# MP3_8xMulti_V1_0.net
KiCad netlist of a schematic drawn in EAGLE
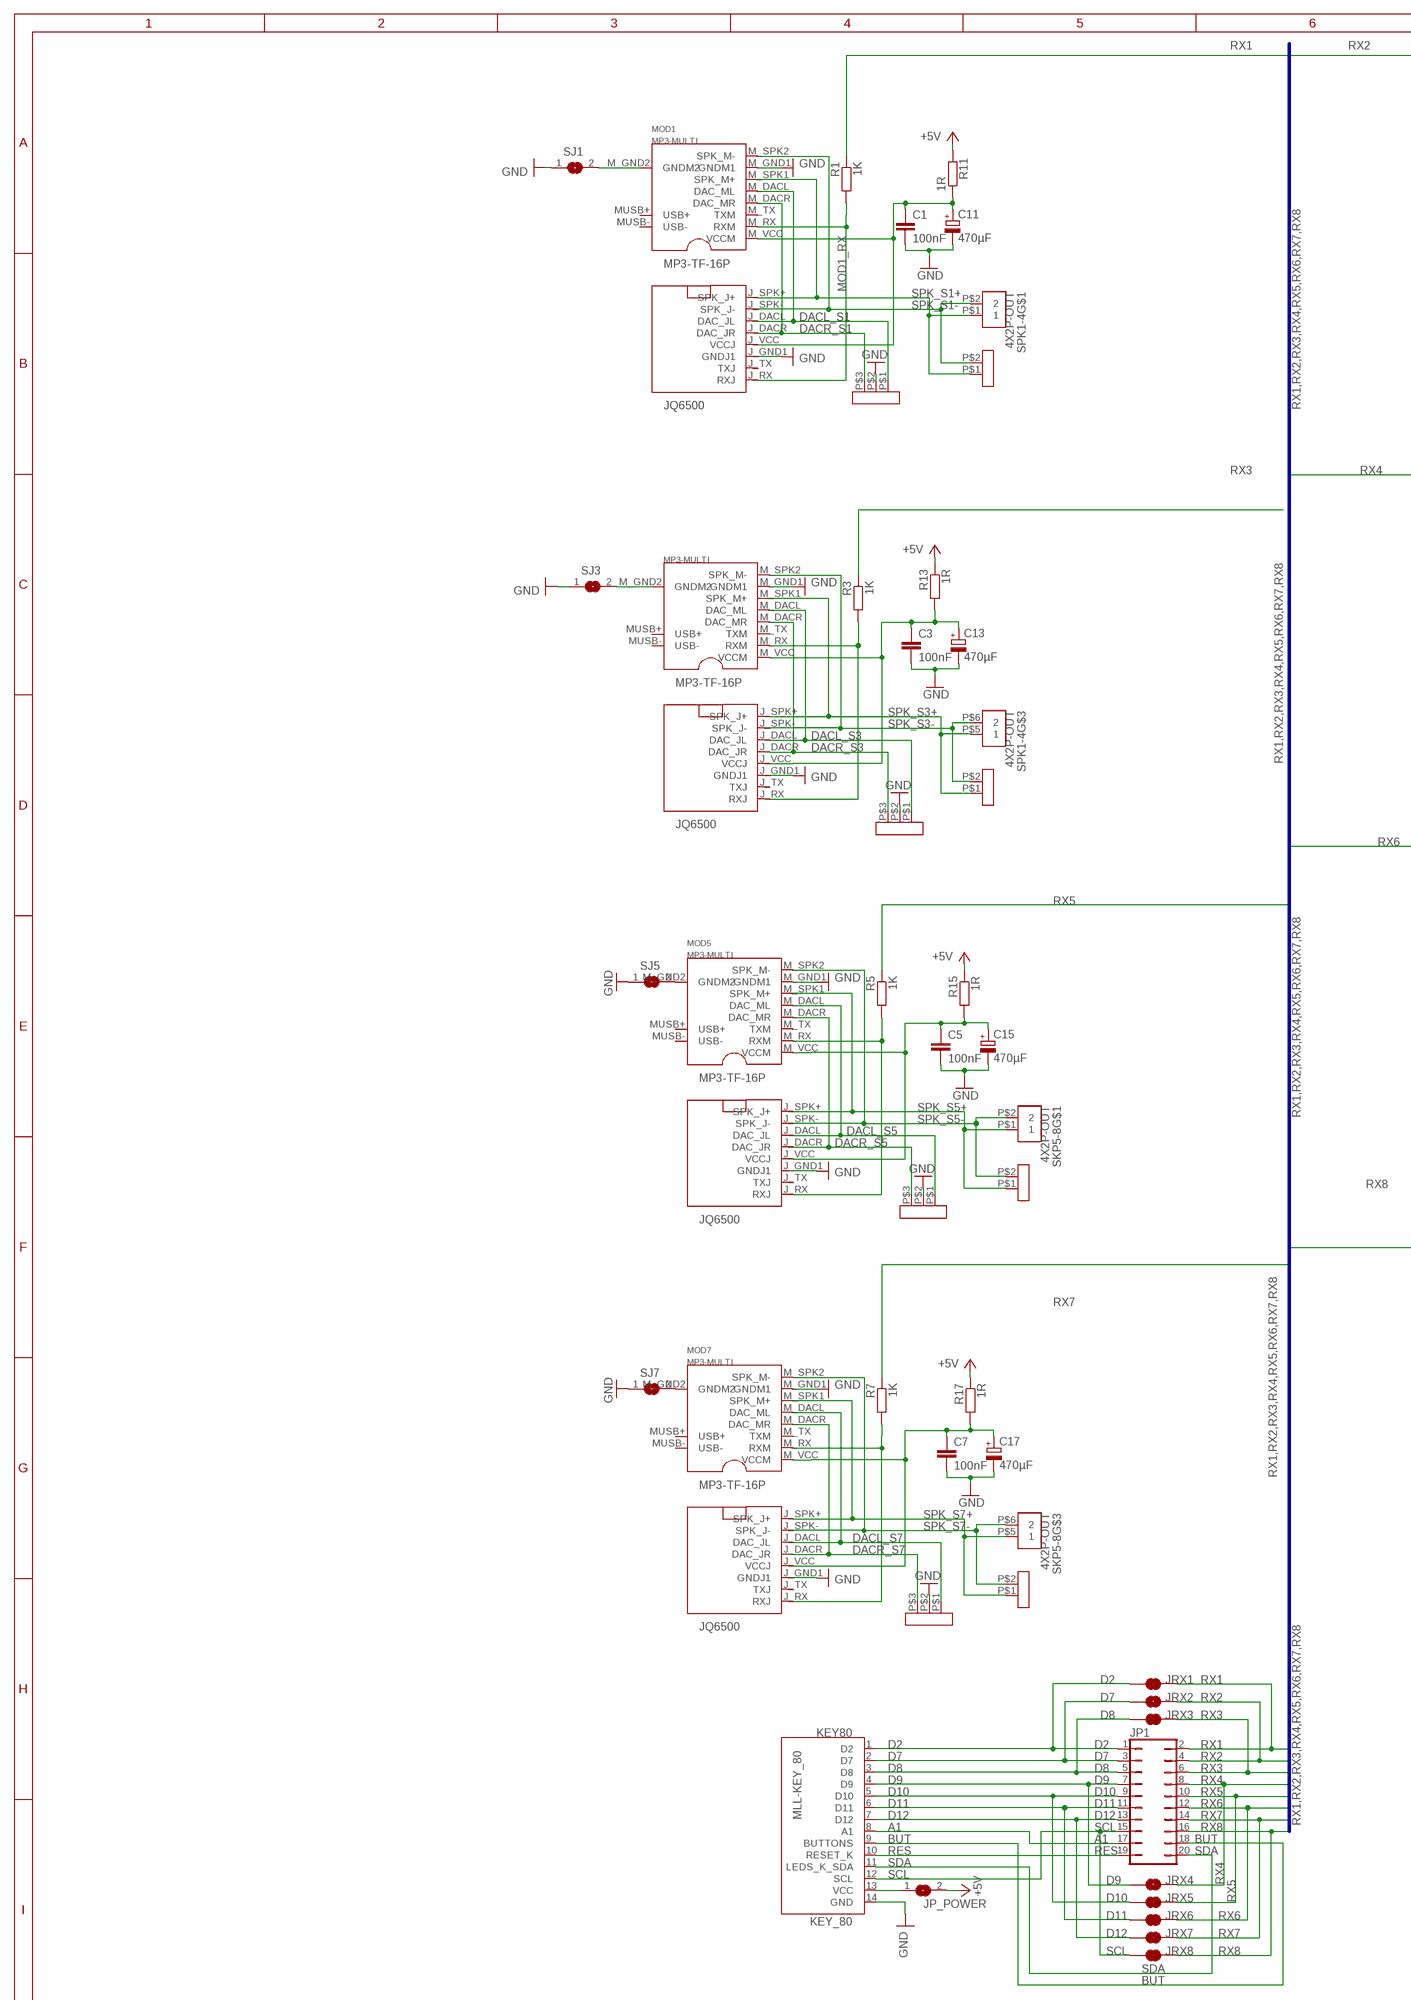
[diagram p0: schematic, sheet 1, part 1 of 2]
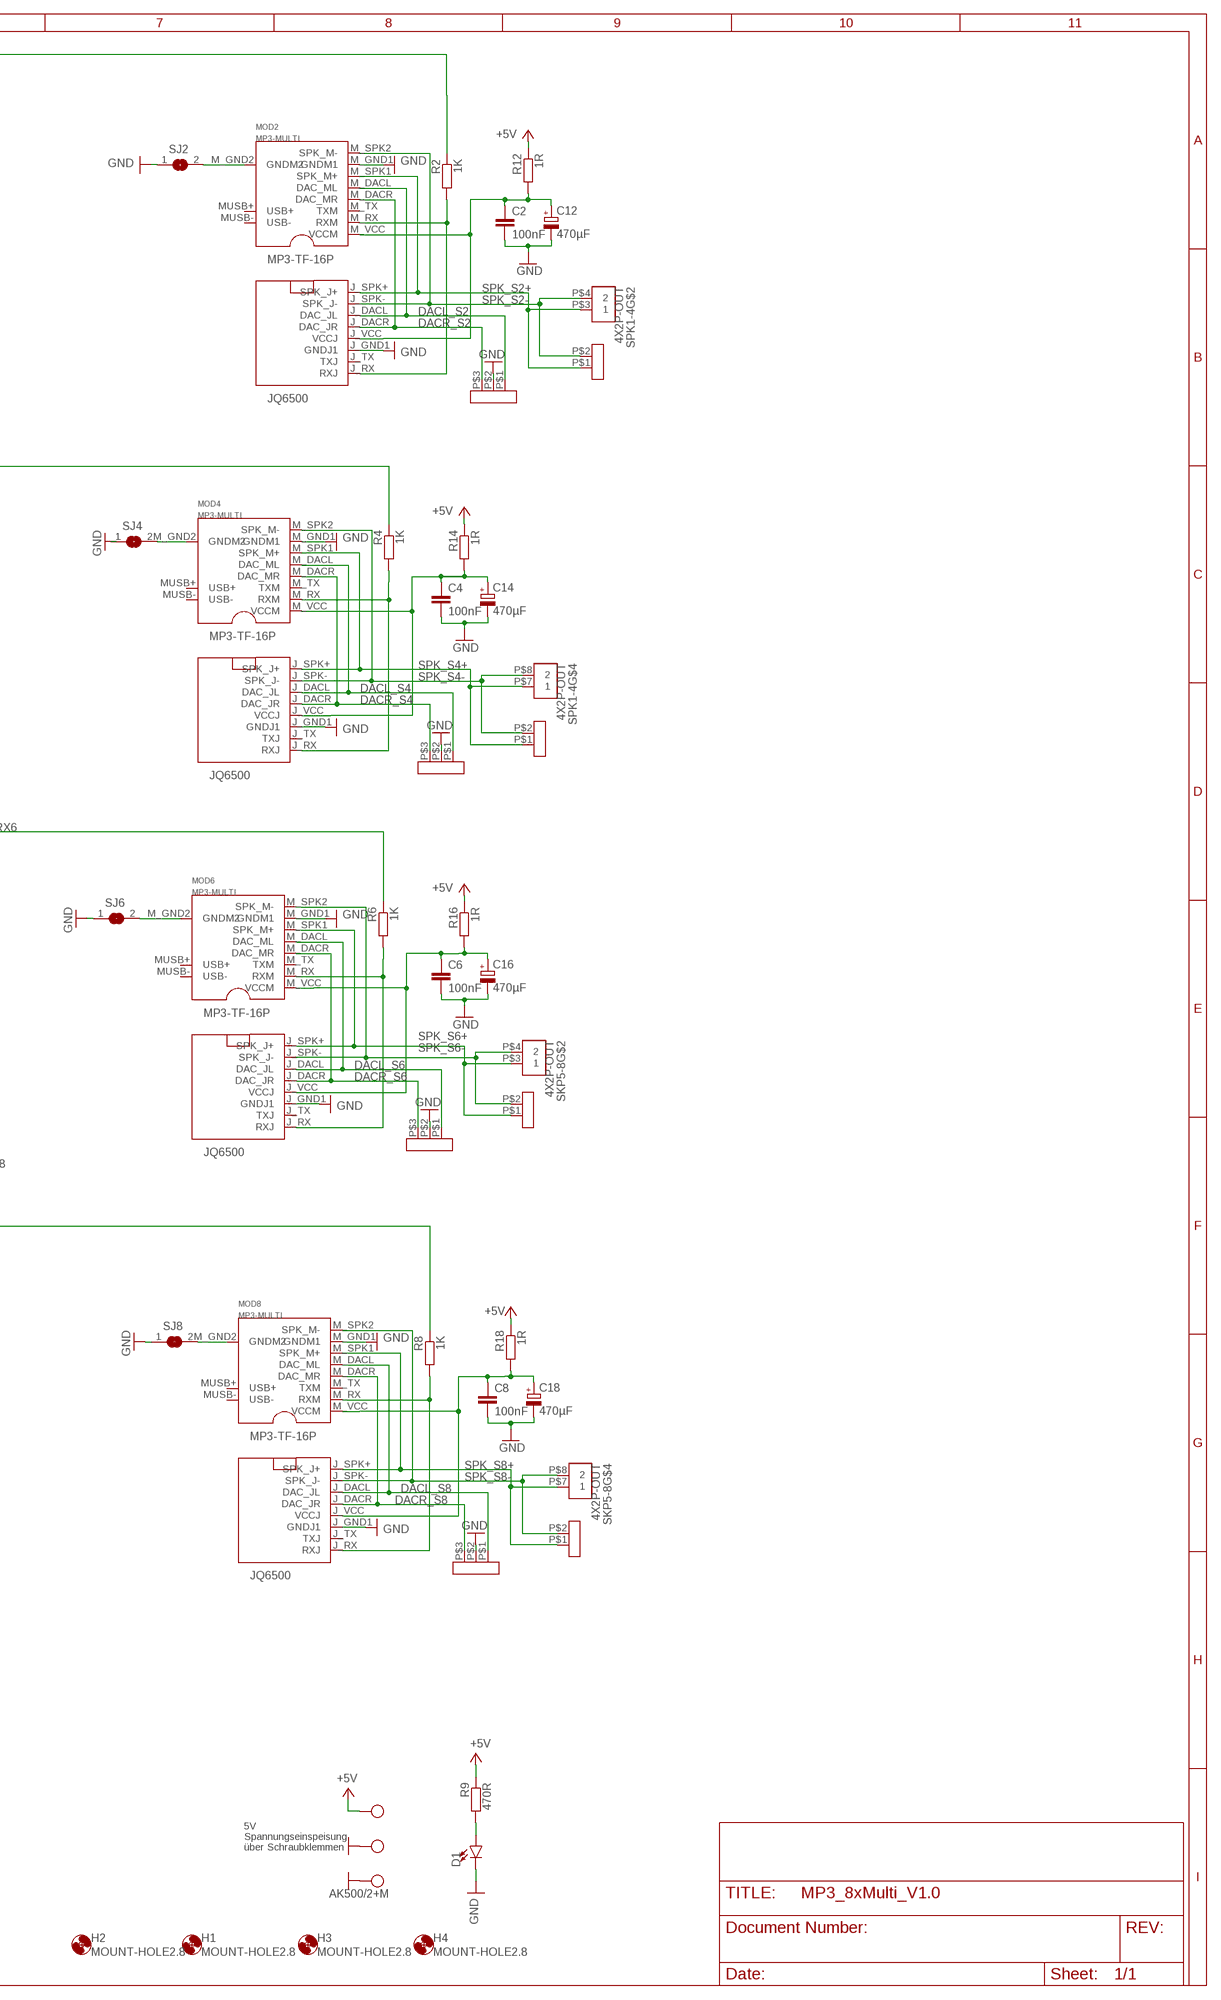
[diagram p1: schematic, sheet 1, part 2 of 2]

(export (version "E")
  (design (tool "Eeschema 10.0.6"))
  (components
    (comp (ref "C1")
      (value "100nF")
      (footprint "eagle-import:C025-025X050")
      (libsource (lib "eagle-import") (part "C-EU025-025X050"))
    )
    (comp (ref "C2")
      (value "100nF")
      (footprint "eagle-import:C025-025X050")
      (libsource (lib "eagle-import") (part "C-EU025-025X050"))
    )
    (comp (ref "C3")
      (value "100nF")
      (footprint "eagle-import:C025-025X050")
      (libsource (lib "eagle-import") (part "C-EU025-025X050"))
    )
    (comp (ref "C4")
      (value "100nF")
      (footprint "eagle-import:C025-025X050")
      (libsource (lib "eagle-import") (part "C-EU025-025X050"))
    )
    (comp (ref "C5")
      (value "100nF")
      (footprint "eagle-import:C025-025X050")
      (libsource (lib "eagle-import") (part "C-EU025-025X050"))
    )
    (comp (ref "C6")
      (value "100nF")
      (footprint "eagle-import:C025-025X050")
      (libsource (lib "eagle-import") (part "C-EU025-025X050"))
    )
    (comp (ref "C7")
      (value "100nF")
      (footprint "eagle-import:C025-025X050")
      (libsource (lib "eagle-import") (part "C-EU025-025X050"))
    )
    (comp (ref "C8")
      (value "100nF")
      (footprint "eagle-import:C025-025X050")
      (libsource (lib "eagle-import") (part "C-EU025-025X050"))
    )
    (comp (ref "C11")
      (value "470µF")
      (footprint "eagle-import:E5-8,5")
      (libsource (lib "eagle-import") (part "CPOL-EUE5-8.5"))
    )
    (comp (ref "C12")
      (value "470µF")
      (footprint "eagle-import:E5-8,5")
      (libsource (lib "eagle-import") (part "CPOL-EUE5-8.5"))
    )
    (comp (ref "C13")
      (value "470µF")
      (footprint "eagle-import:E5-8,5")
      (libsource (lib "eagle-import") (part "CPOL-EUE5-8.5"))
    )
    (comp (ref "C14")
      (value "470µF")
      (footprint "eagle-import:E5-8,5")
      (libsource (lib "eagle-import") (part "CPOL-EUE5-8.5"))
    )
    (comp (ref "C15")
      (value "470µF")
      (footprint "eagle-import:E5-8,5")
      (libsource (lib "eagle-import") (part "CPOL-EUE5-8.5"))
    )
    (comp (ref "C16")
      (value "470µF")
      (footprint "eagle-import:E5-8,5")
      (libsource (lib "eagle-import") (part "CPOL-EUE5-8.5"))
    )
    (comp (ref "C17")
      (value "470µF")
      (footprint "eagle-import:E5-8,5")
      (libsource (lib "eagle-import") (part "CPOL-EUE5-8.5"))
    )
    (comp (ref "C18")
      (value "470µF")
      (footprint "eagle-import:E5-8,5")
      (libsource (lib "eagle-import") (part "CPOL-EUE5-8.5"))
    )
    (comp (ref "D1")
      (value "LED3MM")
      (footprint "eagle-import:LED_3MM")
      (libsource (lib "eagle-import") (part "LED3MM"))
    )
    (comp (ref "DAC1")
      (value "3XRM254")
      (footprint "eagle-import:3XRM254")
      (libsource (lib "eagle-import") (part "3XRM254"))
    )
    (comp (ref "DAC2")
      (value "3XRM254")
      (footprint "eagle-import:3XRM254")
      (libsource (lib "eagle-import") (part "3XRM254"))
    )
    (comp (ref "DAC3")
      (value "3XRM254")
      (footprint "eagle-import:3XRM254")
      (libsource (lib "eagle-import") (part "3XRM254"))
    )
    (comp (ref "DAC4")
      (value "3XRM254")
      (footprint "eagle-import:3XRM254")
      (libsource (lib "eagle-import") (part "3XRM254"))
    )
    (comp (ref "DAC5")
      (value "3XRM254")
      (footprint "eagle-import:3XRM254")
      (libsource (lib "eagle-import") (part "3XRM254"))
    )
    (comp (ref "DAC6")
      (value "3XRM254")
      (footprint "eagle-import:3XRM254")
      (libsource (lib "eagle-import") (part "3XRM254"))
    )
    (comp (ref "DAC7")
      (value "3XRM254")
      (footprint "eagle-import:3XRM254")
      (libsource (lib "eagle-import") (part "3XRM254"))
    )
    (comp (ref "DAC8")
      (value "3XRM254")
      (footprint "eagle-import:3XRM254")
      (libsource (lib "eagle-import") (part "3XRM254"))
    )
    (comp (ref "H1")
      (value "MOUNT-HOLE2.8")
      (footprint "eagle-import:2,8")
      (libsource (lib "eagle-import") (part "MOUNT-HOLE2.8"))
    )
    (comp (ref "H2")
      (value "MOUNT-HOLE2.8")
      (footprint "eagle-import:2,8")
      (libsource (lib "eagle-import") (part "MOUNT-HOLE2.8"))
    )
    (comp (ref "H3")
      (value "MOUNT-HOLE2.8")
      (footprint "eagle-import:2,8")
      (libsource (lib "eagle-import") (part "MOUNT-HOLE2.8"))
    )
    (comp (ref "H4")
      (value "MOUNT-HOLE2.8")
      (footprint "eagle-import:2,8")
      (libsource (lib "eagle-import") (part "MOUNT-HOLE2.8"))
    )
    (comp (ref "JP1")
      (value "JP10Q")
      (footprint "eagle-import:JP10Q")
      (libsource (lib "eagle-import") (part "JP10Q"))
    )
    (comp (ref "JP_POWER")
      (value "SJ")
      (footprint "eagle-import:SJ")
      (libsource (lib "eagle-import") (part "SJ"))
    )
    (comp (ref "JRX1")
      (value "JUMPER-SMT_2_NC_TRACE_NO-SILK")
      (footprint "eagle-import:SMT-JUMPER_2_NC_TRACE_NO-SILK")
      (libsource (lib "eagle-import") (part "JUMPER-SMT_2_NC_TRACE_NO-SILK"))
    )
    (comp (ref "JRX2")
      (value "JUMPER-SMT_2_NC_TRACE_NO-SILK")
      (footprint "eagle-import:SMT-JUMPER_2_NC_TRACE_NO-SILK")
      (libsource (lib "eagle-import") (part "JUMPER-SMT_2_NC_TRACE_NO-SILK"))
    )
    (comp (ref "JRX3")
      (value "JUMPER-SMT_2_NC_TRACE_NO-SILK")
      (footprint "eagle-import:SMT-JUMPER_2_NC_TRACE_NO-SILK")
      (libsource (lib "eagle-import") (part "JUMPER-SMT_2_NC_TRACE_NO-SILK"))
    )
    (comp (ref "JRX4")
      (value "JUMPER-SMT_2_NC_TRACE_NO-SILK")
      (footprint "eagle-import:SMT-JUMPER_2_NC_TRACE_NO-SILK")
      (libsource (lib "eagle-import") (part "JUMPER-SMT_2_NC_TRACE_NO-SILK"))
    )
    (comp (ref "JRX5")
      (value "JUMPER-SMT_2_NC_TRACE_NO-SILK")
      (footprint "eagle-import:SMT-JUMPER_2_NC_TRACE_NO-SILK")
      (libsource (lib "eagle-import") (part "JUMPER-SMT_2_NC_TRACE_NO-SILK"))
    )
    (comp (ref "JRX6")
      (value "JUMPER-SMT_2_NC_TRACE_NO-SILK")
      (footprint "eagle-import:SMT-JUMPER_2_NC_TRACE_NO-SILK")
      (libsource (lib "eagle-import") (part "JUMPER-SMT_2_NC_TRACE_NO-SILK"))
    )
    (comp (ref "JRX7")
      (value "JUMPER-SMT_2_NC_TRACE_NO-SILK")
      (footprint "eagle-import:SMT-JUMPER_2_NC_TRACE_NO-SILK")
      (libsource (lib "eagle-import") (part "JUMPER-SMT_2_NC_TRACE_NO-SILK"))
    )
    (comp (ref "JRX8")
      (value "JUMPER-SMT_2_NC_TRACE_NO-SILK")
      (footprint "eagle-import:SMT-JUMPER_2_NC_TRACE_NO-SILK")
      (libsource (lib "eagle-import") (part "JUMPER-SMT_2_NC_TRACE_NO-SILK"))
    )
    (comp (ref "KEY80")
      (value "KEY_80")
      (footprint "eagle-import:IDC14")
      (libsource (lib "eagle-import") (part "KEY_80"))
    )
    (comp (ref "MOD1")
      (value "MP3-MULTI")
      (footprint "eagle-import:MP3-TF16P_JQ6500")
      (libsource (lib "eagle-import") (part "MP3-MULTI"))
    )
    (comp (ref "MOD2")
      (value "MP3-MULTI")
      (footprint "eagle-import:MP3-TF16P_JQ6500")
      (libsource (lib "eagle-import") (part "MP3-MULTI"))
    )
    (comp (ref "MOD3")
      (value "MP3-MULTI")
      (footprint "eagle-import:MP3-TF16P_JQ6500")
      (libsource (lib "eagle-import") (part "MP3-MULTI"))
    )
    (comp (ref "MOD4")
      (value "MP3-MULTI")
      (footprint "eagle-import:MP3-TF16P_JQ6500")
      (libsource (lib "eagle-import") (part "MP3-MULTI"))
    )
    (comp (ref "MOD5")
      (value "MP3-MULTI")
      (footprint "eagle-import:MP3-TF16P_JQ6500")
      (libsource (lib "eagle-import") (part "MP3-MULTI"))
    )
    (comp (ref "MOD6")
      (value "MP3-MULTI")
      (footprint "eagle-import:MP3-TF16P_JQ6500")
      (libsource (lib "eagle-import") (part "MP3-MULTI"))
    )
    (comp (ref "MOD7")
      (value "MP3-MULTI")
      (footprint "eagle-import:MP3-TF16P_JQ6500")
      (libsource (lib "eagle-import") (part "MP3-MULTI"))
    )
    (comp (ref "MOD8")
      (value "MP3-MULTI")
      (footprint "eagle-import:MP3-TF16P_JQ6500")
      (libsource (lib "eagle-import") (part "MP3-MULTI"))
    )
    (comp (ref "R1")
      (value "1K")
      (footprint "eagle-import:0207_7")
      (libsource (lib "eagle-import") (part "R-EU_0207/7"))
    )
    (comp (ref "R2")
      (value "1K")
      (footprint "eagle-import:0207_7")
      (libsource (lib "eagle-import") (part "R-EU_0207/7"))
    )
    (comp (ref "R3")
      (value "1K")
      (footprint "eagle-import:0207_7")
      (libsource (lib "eagle-import") (part "R-EU_0207/7"))
    )
    (comp (ref "R4")
      (value "1K")
      (footprint "eagle-import:0207_7")
      (libsource (lib "eagle-import") (part "R-EU_0207/7"))
    )
    (comp (ref "R5")
      (value "1K")
      (footprint "eagle-import:0207_7")
      (libsource (lib "eagle-import") (part "R-EU_0207/7"))
    )
    (comp (ref "R6")
      (value "1K")
      (footprint "eagle-import:0207_7")
      (libsource (lib "eagle-import") (part "R-EU_0207/7"))
    )
    (comp (ref "R7")
      (value "1K")
      (footprint "eagle-import:0207_7")
      (libsource (lib "eagle-import") (part "R-EU_0207/7"))
    )
    (comp (ref "R8")
      (value "1K")
      (footprint "eagle-import:0207_7")
      (libsource (lib "eagle-import") (part "R-EU_0207/7"))
    )
    (comp (ref "R9")
      (value "470R")
      (footprint "eagle-import:0207_7")
      (libsource (lib "eagle-import") (part "R-EU_0207/7"))
    )
    (comp (ref "R11")
      (value "1R")
      (footprint "eagle-import:0207_7")
      (libsource (lib "eagle-import") (part "R-EU_0207/7"))
    )
    (comp (ref "R12")
      (value "1R")
      (footprint "eagle-import:0207_7")
      (libsource (lib "eagle-import") (part "R-EU_0207/7"))
    )
    (comp (ref "R13")
      (value "1R")
      (footprint "eagle-import:0207_7")
      (libsource (lib "eagle-import") (part "R-EU_0207/7"))
    )
    (comp (ref "R14")
      (value "1R")
      (footprint "eagle-import:0207_7")
      (libsource (lib "eagle-import") (part "R-EU_0207/7"))
    )
    (comp (ref "R15")
      (value "1R")
      (footprint "eagle-import:0207_7")
      (libsource (lib "eagle-import") (part "R-EU_0207/7"))
    )
    (comp (ref "R16")
      (value "1R")
      (footprint "eagle-import:0207_7")
      (libsource (lib "eagle-import") (part "R-EU_0207/7"))
    )
    (comp (ref "R17")
      (value "1R")
      (footprint "eagle-import:0207_7")
      (libsource (lib "eagle-import") (part "R-EU_0207/7"))
    )
    (comp (ref "R18")
      (value "1R")
      (footprint "eagle-import:0207_7")
      (libsource (lib "eagle-import") (part "R-EU_0207/7"))
    )
    (comp (ref "SJ1") (value "SJ") (footprint "eagle-import:SJ") (libsource (lib "eagle-import") (part "SJ")))
    (comp (ref "SJ2") (value "SJ") (footprint "eagle-import:SJ") (libsource (lib "eagle-import") (part "SJ")))
    (comp (ref "SJ3") (value "SJ") (footprint "eagle-import:SJ") (libsource (lib "eagle-import") (part "SJ")))
    (comp (ref "SJ4") (value "SJ") (footprint "eagle-import:SJ") (libsource (lib "eagle-import") (part "SJ")))
    (comp (ref "SJ5") (value "SJ") (footprint "eagle-import:SJ") (libsource (lib "eagle-import") (part "SJ")))
    (comp (ref "SJ6") (value "SJ") (footprint "eagle-import:SJ") (libsource (lib "eagle-import") (part "SJ")))
    (comp (ref "SJ7") (value "SJ") (footprint "eagle-import:SJ") (libsource (lib "eagle-import") (part "SJ")))
    (comp (ref "SJ8") (value "SJ") (footprint "eagle-import:SJ") (libsource (lib "eagle-import") (part "SJ")))
    (comp (ref "SKP5-8")
      (value "4X2P-OUT")
      (footprint "eagle-import:DG308")
      (libsource (lib "eagle-import") (part "4X2P-OUT"))
    )
    (comp (ref "SPK1")
      (value "2XRM254")
      (footprint "eagle-import:2XRM254")
      (libsource (lib "eagle-import") (part "2XRM254"))
    )
    (comp (ref "SPK1-4")
      (value "4X2P-OUT")
      (footprint "eagle-import:DG308")
      (libsource (lib "eagle-import") (part "4X2P-OUT"))
    )
    (comp (ref "SPK2")
      (value "2XRM254")
      (footprint "eagle-import:2XRM254")
      (libsource (lib "eagle-import") (part "2XRM254"))
    )
    (comp (ref "SPK3")
      (value "2XRM254")
      (footprint "eagle-import:2XRM254")
      (libsource (lib "eagle-import") (part "2XRM254"))
    )
    (comp (ref "SPK4")
      (value "2XRM254")
      (footprint "eagle-import:2XRM254")
      (libsource (lib "eagle-import") (part "2XRM254"))
    )
    (comp (ref "SPK5")
      (value "2XRM254")
      (footprint "eagle-import:2XRM254")
      (libsource (lib "eagle-import") (part "2XRM254"))
    )
    (comp (ref "SPK6")
      (value "2XRM254")
      (footprint "eagle-import:2XRM254")
      (libsource (lib "eagle-import") (part "2XRM254"))
    )
    (comp (ref "SPK7")
      (value "2XRM254")
      (footprint "eagle-import:2XRM254")
      (libsource (lib "eagle-import") (part "2XRM254"))
    )
    (comp (ref "SPK8")
      (value "2XRM254")
      (footprint "eagle-import:2XRM254")
      (libsource (lib "eagle-import") (part "2XRM254"))
    )
    (comp (ref "X1")
      (value "AK500/2+M")
      (footprint "eagle-import:AK500_2+M")
      (libsource (lib "eagle-import") (part "AK500/2+M"))
    )
  )
  (nets
    (net (code "1") (name "+5V") (class "Default")
      (node (ref "JP_POWER") (pin "2") (pinfunction "2_2") (pintype "passive"))
      (node (ref "R11") (pin "2") (pinfunction "2_2") (pintype "passive"))
      (node (ref "R12") (pin "1") (pinfunction "1_1") (pintype "passive"))
      (node (ref "R13") (pin "1") (pinfunction "1_1") (pintype "passive"))
      (node (ref "R14") (pin "1") (pinfunction "1_1") (pintype "passive"))
      (node (ref "R15") (pin "1") (pinfunction "1_1") (pintype "passive"))
      (node (ref "R16") (pin "1") (pinfunction "1_1") (pintype "passive"))
      (node (ref "R17") (pin "1") (pinfunction "1_1") (pintype "passive"))
      (node (ref "R18") (pin "1") (pinfunction "1_1") (pintype "passive"))
      (node (ref "R9") (pin "1") (pinfunction "1_1") (pintype "passive"))
      (node (ref "X1") (pin "2") (pinfunction "KL_2") (pintype "passive"))
    )
    (net (code "2") (name "/A1") (class "Default")
      (node (ref "JP1") (pin "17") (pinfunction "17_17") (pintype "passive"))
      (node (ref "KEY80") (pin "8") (pinfunction "A1_8") (pintype "bidirectional"))
    )
    (net (code "3") (name "/BUT") (class "Default")
      (node (ref "JP1") (pin "18") (pinfunction "18_18") (pintype "passive"))
      (node (ref "KEY80") (pin "9") (pinfunction "BUTTONS_9") (pintype "bidirectional"))
    )
    (net (code "4") (name "/D2") (class "Default")
      (node (ref "JP1") (pin "1") (pinfunction "1_1") (pintype "passive"))
      (node (ref "JRX1") (pin "1") (pinfunction "1_1") (pintype "passive"))
      (node (ref "KEY80") (pin "1") (pinfunction "D2_1") (pintype "bidirectional"))
    )
    (net (code "5") (name "/D7") (class "Default")
      (node (ref "JP1") (pin "3") (pinfunction "3_3") (pintype "passive"))
      (node (ref "JRX2") (pin "1") (pinfunction "1_1") (pintype "passive"))
      (node (ref "KEY80") (pin "2") (pinfunction "D7_2") (pintype "bidirectional"))
    )
    (net (code "6") (name "/D8") (class "Default")
      (node (ref "JP1") (pin "5") (pinfunction "5_5") (pintype "passive"))
      (node (ref "JRX3") (pin "1") (pinfunction "1_1") (pintype "passive"))
      (node (ref "KEY80") (pin "3") (pinfunction "D8_3") (pintype "bidirectional"))
    )
    (net (code "7") (name "/D9") (class "Default")
      (node (ref "JP1") (pin "7") (pinfunction "7_7") (pintype "passive"))
      (node (ref "JRX4") (pin "1") (pinfunction "1_1") (pintype "passive"))
      (node (ref "KEY80") (pin "4") (pinfunction "D9_4") (pintype "bidirectional"))
    )
    (net (code "8") (name "/D10") (class "Default")
      (node (ref "JP1") (pin "9") (pinfunction "9_9") (pintype "passive"))
      (node (ref "JRX5") (pin "1") (pinfunction "1_1") (pintype "passive"))
      (node (ref "KEY80") (pin "5") (pinfunction "D10_5") (pintype "bidirectional"))
    )
    (net (code "9") (name "/D11") (class "Default")
      (node (ref "JP1") (pin "11") (pinfunction "11_11") (pintype "passive"))
      (node (ref "JRX6") (pin "1") (pinfunction "1_1") (pintype "passive"))
      (node (ref "KEY80") (pin "6") (pinfunction "D11_6") (pintype "bidirectional"))
    )
    (net (code "10") (name "/D12") (class "Default")
      (node (ref "JP1") (pin "13") (pinfunction "13_13") (pintype "passive"))
      (node (ref "JRX7") (pin "1") (pinfunction "1_1") (pintype "passive"))
      (node (ref "KEY80") (pin "7") (pinfunction "D12_7") (pintype "bidirectional"))
    )
    (net (code "11") (name "/DACL_S1") (class "Default")
      (node (ref "DAC1") (pin "P$1") (pinfunction "P$1_P$1") (pintype "bidirectional"))
      (node (ref "MOD1") (pin "J_DACL") (pinfunction "DAC_JL_J_DACL") (pintype "bidirectional"))
      (node (ref "MOD1") (pin "M_DACL") (pinfunction "DAC_ML_M_DACL") (pintype "bidirectional"))
    )
    (net (code "12") (name "/DACL_S2") (class "Default")
      (node (ref "DAC2") (pin "P$1") (pinfunction "P$1_P$1") (pintype "bidirectional"))
      (node (ref "MOD2") (pin "J_DACL") (pinfunction "DAC_JL_J_DACL") (pintype "bidirectional"))
      (node (ref "MOD2") (pin "M_DACL") (pinfunction "DAC_ML_M_DACL") (pintype "bidirectional"))
    )
    (net (code "13") (name "/DACL_S3") (class "Default")
      (node (ref "DAC3") (pin "P$1") (pinfunction "P$1_P$1") (pintype "bidirectional"))
      (node (ref "MOD3") (pin "J_DACL") (pinfunction "DAC_JL_J_DACL") (pintype "bidirectional"))
      (node (ref "MOD3") (pin "M_DACL") (pinfunction "DAC_ML_M_DACL") (pintype "bidirectional"))
    )
    (net (code "14") (name "/DACL_S4") (class "Default")
      (node (ref "DAC4") (pin "P$1") (pinfunction "P$1_P$1") (pintype "bidirectional"))
      (node (ref "MOD4") (pin "J_DACL") (pinfunction "DAC_JL_J_DACL") (pintype "bidirectional"))
      (node (ref "MOD4") (pin "M_DACL") (pinfunction "DAC_ML_M_DACL") (pintype "bidirectional"))
    )
    (net (code "15") (name "/DACL_S5") (class "Default")
      (node (ref "DAC5") (pin "P$1") (pinfunction "P$1_P$1") (pintype "bidirectional"))
      (node (ref "MOD5") (pin "J_DACL") (pinfunction "DAC_JL_J_DACL") (pintype "bidirectional"))
      (node (ref "MOD5") (pin "M_DACL") (pinfunction "DAC_ML_M_DACL") (pintype "bidirectional"))
    )
    (net (code "16") (name "/DACL_S6") (class "Default")
      (node (ref "DAC6") (pin "P$1") (pinfunction "P$1_P$1") (pintype "bidirectional"))
      (node (ref "MOD6") (pin "J_DACL") (pinfunction "DAC_JL_J_DACL") (pintype "bidirectional"))
      (node (ref "MOD6") (pin "M_DACL") (pinfunction "DAC_ML_M_DACL") (pintype "bidirectional"))
    )
    (net (code "17") (name "/DACL_S7") (class "Default")
      (node (ref "DAC7") (pin "P$1") (pinfunction "P$1_P$1") (pintype "bidirectional"))
      (node (ref "MOD7") (pin "J_DACL") (pinfunction "DAC_JL_J_DACL") (pintype "bidirectional"))
      (node (ref "MOD7") (pin "M_DACL") (pinfunction "DAC_ML_M_DACL") (pintype "bidirectional"))
    )
    (net (code "18") (name "/DACL_S8") (class "Default")
      (node (ref "DAC8") (pin "P$1") (pinfunction "P$1_P$1") (pintype "bidirectional"))
      (node (ref "MOD8") (pin "J_DACL") (pinfunction "DAC_JL_J_DACL") (pintype "bidirectional"))
      (node (ref "MOD8") (pin "M_DACL") (pinfunction "DAC_ML_M_DACL") (pintype "bidirectional"))
    )
    (net (code "19") (name "/DACR_S1") (class "Default")
      (node (ref "DAC1") (pin "P$3") (pinfunction "P$3_P$3") (pintype "bidirectional"))
      (node (ref "MOD1") (pin "J_DACR") (pinfunction "DAC_JR_J_DACR") (pintype "bidirectional"))
      (node (ref "MOD1") (pin "M_DACR") (pinfunction "DAC_MR_M_DACR") (pintype "bidirectional"))
    )
    (net (code "20") (name "/DACR_S2") (class "Default")
      (node (ref "DAC2") (pin "P$3") (pinfunction "P$3_P$3") (pintype "bidirectional"))
      (node (ref "MOD2") (pin "J_DACR") (pinfunction "DAC_JR_J_DACR") (pintype "bidirectional"))
      (node (ref "MOD2") (pin "M_DACR") (pinfunction "DAC_MR_M_DACR") (pintype "bidirectional"))
    )
    (net (code "21") (name "/DACR_S3") (class "Default")
      (node (ref "DAC3") (pin "P$3") (pinfunction "P$3_P$3") (pintype "bidirectional"))
      (node (ref "MOD3") (pin "J_DACR") (pinfunction "DAC_JR_J_DACR") (pintype "bidirectional"))
      (node (ref "MOD3") (pin "M_DACR") (pinfunction "DAC_MR_M_DACR") (pintype "bidirectional"))
    )
    (net (code "22") (name "/DACR_S4") (class "Default")
      (node (ref "DAC4") (pin "P$3") (pinfunction "P$3_P$3") (pintype "bidirectional"))
      (node (ref "MOD4") (pin "J_DACR") (pinfunction "DAC_JR_J_DACR") (pintype "bidirectional"))
      (node (ref "MOD4") (pin "M_DACR") (pinfunction "DAC_MR_M_DACR") (pintype "bidirectional"))
    )
    (net (code "23") (name "/DACR_S5") (class "Default")
      (node (ref "DAC5") (pin "P$3") (pinfunction "P$3_P$3") (pintype "bidirectional"))
      (node (ref "MOD5") (pin "J_DACR") (pinfunction "DAC_JR_J_DACR") (pintype "bidirectional"))
      (node (ref "MOD5") (pin "M_DACR") (pinfunction "DAC_MR_M_DACR") (pintype "bidirectional"))
    )
    (net (code "24") (name "/DACR_S6") (class "Default")
      (node (ref "DAC6") (pin "P$3") (pinfunction "P$3_P$3") (pintype "bidirectional"))
      (node (ref "MOD6") (pin "J_DACR") (pinfunction "DAC_JR_J_DACR") (pintype "bidirectional"))
      (node (ref "MOD6") (pin "M_DACR") (pinfunction "DAC_MR_M_DACR") (pintype "bidirectional"))
    )
    (net (code "25") (name "/DACR_S7") (class "Default")
      (node (ref "DAC7") (pin "P$3") (pinfunction "P$3_P$3") (pintype "bidirectional"))
      (node (ref "MOD7") (pin "J_DACR") (pinfunction "DAC_JR_J_DACR") (pintype "bidirectional"))
      (node (ref "MOD7") (pin "M_DACR") (pinfunction "DAC_MR_M_DACR") (pintype "bidirectional"))
    )
    (net (code "26") (name "/DACR_S8") (class "Default")
      (node (ref "DAC8") (pin "P$3") (pinfunction "P$3_P$3") (pintype "bidirectional"))
      (node (ref "MOD8") (pin "J_DACR") (pinfunction "DAC_JR_J_DACR") (pintype "bidirectional"))
      (node (ref "MOD8") (pin "M_DACR") (pinfunction "DAC_MR_M_DACR") (pintype "bidirectional"))
    )
    (net (code "27") (name "/MOD1_RX") (class "Default")
      (node (ref "MOD1") (pin "J_RX") (pinfunction "RXJ_J_RX") (pintype "bidirectional"))
      (node (ref "MOD1") (pin "M_RX") (pinfunction "RXM_M_RX") (pintype "bidirectional"))
      (node (ref "R1") (pin "2") (pinfunction "2_2") (pintype "passive"))
    )
    (net (code "28") (name "/RES") (class "Default")
      (node (ref "JP1") (pin "19") (pinfunction "19_19") (pintype "passive"))
      (node (ref "KEY80") (pin "10") (pinfunction "RESET_K_10") (pintype "bidirectional"))
    )
    (net (code "29") (name "/RX1") (class "Default")
      (node (ref "JP1") (pin "2") (pinfunction "2_2") (pintype "passive"))
      (node (ref "JRX1") (pin "2") (pinfunction "2_2") (pintype "passive"))
      (node (ref "R1") (pin "1") (pinfunction "1_1") (pintype "passive"))
    )
    (net (code "30") (name "/RX2") (class "Default")
      (node (ref "JP1") (pin "4") (pinfunction "4_4") (pintype "passive"))
      (node (ref "JRX2") (pin "2") (pinfunction "2_2") (pintype "passive"))
      (node (ref "R2") (pin "1") (pinfunction "1_1") (pintype "passive"))
    )
    (net (code "31") (name "/RX3") (class "Default")
      (node (ref "JP1") (pin "6") (pinfunction "6_6") (pintype "passive"))
      (node (ref "JRX3") (pin "2") (pinfunction "2_2") (pintype "passive"))
      (node (ref "R3") (pin "1") (pinfunction "1_1") (pintype "passive"))
    )
    (net (code "32") (name "/RX4") (class "Default")
      (node (ref "JP1") (pin "8") (pinfunction "8_8") (pintype "passive"))
      (node (ref "JRX4") (pin "2") (pinfunction "2_2") (pintype "passive"))
      (node (ref "R4") (pin "1") (pinfunction "1_1") (pintype "passive"))
    )
    (net (code "33") (name "/RX5") (class "Default")
      (node (ref "JP1") (pin "10") (pinfunction "10_10") (pintype "passive"))
      (node (ref "JRX5") (pin "2") (pinfunction "2_2") (pintype "passive"))
      (node (ref "R5") (pin "1") (pinfunction "1_1") (pintype "passive"))
    )
    (net (code "34") (name "/RX6") (class "Default")
      (node (ref "JP1") (pin "12") (pinfunction "12_12") (pintype "passive"))
      (node (ref "JRX6") (pin "2") (pinfunction "2_2") (pintype "passive"))
      (node (ref "R6") (pin "1") (pinfunction "1_1") (pintype "passive"))
    )
    (net (code "35") (name "/RX7") (class "Default")
      (node (ref "JP1") (pin "14") (pinfunction "14_14") (pintype "passive"))
      (node (ref "JRX7") (pin "2") (pinfunction "2_2") (pintype "passive"))
      (node (ref "R7") (pin "1") (pinfunction "1_1") (pintype "passive"))
    )
    (net (code "36") (name "/RX8") (class "Default")
      (node (ref "JP1") (pin "16") (pinfunction "16_16") (pintype "passive"))
      (node (ref "JRX8") (pin "2") (pinfunction "2_2") (pintype "passive"))
      (node (ref "R8") (pin "1") (pinfunction "1_1") (pintype "passive"))
    )
    (net (code "37") (name "/SCL") (class "Default")
      (node (ref "JP1") (pin "15") (pinfunction "15_15") (pintype "passive"))
      (node (ref "JRX8") (pin "1") (pinfunction "1_1") (pintype "passive"))
      (node (ref "KEY80") (pin "12") (pinfunction "SCL_12") (pintype "bidirectional"))
    )
    (net (code "38") (name "/SDA") (class "Default")
      (node (ref "JP1") (pin "20") (pinfunction "20_20") (pintype "passive"))
      (node (ref "KEY80") (pin "11") (pinfunction "LEDS_K_SDA_11") (pintype "bidirectional"))
    )
    (net (code "39") (name "/SPK_S1+") (class "Default")
      (node (ref "MOD1") (pin "J_SPK+") (pinfunction "SPK_J+_J_SPK+") (pintype "bidirectional"))
      (node (ref "MOD1") (pin "M_SPK1") (pinfunction "SPK_M+_M_SPK1") (pintype "bidirectional"))
      (node (ref "SPK1") (pin "P$1") (pinfunction "P$1_P$1") (pintype "bidirectional"))
      (node (ref "SPK1-4") (pin "P$1") (pinfunction "1_P$1") (pintype "bidirectional"))
    )
    (net (code "40") (name "/SPK_S1-") (class "Default")
      (node (ref "MOD1") (pin "J_SPK-") (pinfunction "SPK_J-_J_SPK-") (pintype "bidirectional"))
      (node (ref "MOD1") (pin "M_SPK2") (pinfunction "SPK_M-_M_SPK2") (pintype "bidirectional"))
      (node (ref "SPK1") (pin "P$2") (pinfunction "P$2_P$2") (pintype "bidirectional"))
      (node (ref "SPK1-4") (pin "P$2") (pinfunction "2_P$2") (pintype "bidirectional"))
    )
    (net (code "41") (name "/SPK_S2+") (class "Default")
      (node (ref "MOD2") (pin "J_SPK+") (pinfunction "SPK_J+_J_SPK+") (pintype "bidirectional"))
      (node (ref "MOD2") (pin "M_SPK1") (pinfunction "SPK_M+_M_SPK1") (pintype "bidirectional"))
      (node (ref "SPK1-4") (pin "P$3") (pinfunction "1_P$3") (pintype "bidirectional"))
      (node (ref "SPK2") (pin "P$1") (pinfunction "P$1_P$1") (pintype "bidirectional"))
    )
    (net (code "42") (name "/SPK_S2-") (class "Default")
      (node (ref "MOD2") (pin "J_SPK-") (pinfunction "SPK_J-_J_SPK-") (pintype "bidirectional"))
      (node (ref "MOD2") (pin "M_SPK2") (pinfunction "SPK_M-_M_SPK2") (pintype "bidirectional"))
      (node (ref "SPK1-4") (pin "P$4") (pinfunction "2_P$4") (pintype "bidirectional"))
      (node (ref "SPK2") (pin "P$2") (pinfunction "P$2_P$2") (pintype "bidirectional"))
    )
    (net (code "43") (name "/SPK_S3+") (class "Default")
      (node (ref "MOD3") (pin "J_SPK+") (pinfunction "SPK_J+_J_SPK+") (pintype "bidirectional"))
      (node (ref "MOD3") (pin "M_SPK1") (pinfunction "SPK_M+_M_SPK1") (pintype "bidirectional"))
      (node (ref "SPK1-4") (pin "P$5") (pinfunction "1_P$5") (pintype "bidirectional"))
      (node (ref "SPK3") (pin "P$1") (pinfunction "P$1_P$1") (pintype "bidirectional"))
    )
    (net (code "44") (name "/SPK_S3-") (class "Default")
      (node (ref "MOD3") (pin "J_SPK-") (pinfunction "SPK_J-_J_SPK-") (pintype "bidirectional"))
      (node (ref "MOD3") (pin "M_SPK2") (pinfunction "SPK_M-_M_SPK2") (pintype "bidirectional"))
      (node (ref "SPK1-4") (pin "P$6") (pinfunction "2_P$6") (pintype "bidirectional"))
      (node (ref "SPK3") (pin "P$2") (pinfunction "P$2_P$2") (pintype "bidirectional"))
    )
    (net (code "45") (name "/SPK_S4+") (class "Default")
      (node (ref "MOD4") (pin "J_SPK+") (pinfunction "SPK_J+_J_SPK+") (pintype "bidirectional"))
      (node (ref "MOD4") (pin "M_SPK1") (pinfunction "SPK_M+_M_SPK1") (pintype "bidirectional"))
      (node (ref "SPK1-4") (pin "P$7") (pinfunction "1_P$7") (pintype "bidirectional"))
      (node (ref "SPK4") (pin "P$1") (pinfunction "P$1_P$1") (pintype "bidirectional"))
    )
    (net (code "46") (name "/SPK_S4-") (class "Default")
      (node (ref "MOD4") (pin "J_SPK-") (pinfunction "SPK_J-_J_SPK-") (pintype "bidirectional"))
      (node (ref "MOD4") (pin "M_SPK2") (pinfunction "SPK_M-_M_SPK2") (pintype "bidirectional"))
      (node (ref "SPK1-4") (pin "P$8") (pinfunction "2_P$8") (pintype "bidirectional"))
      (node (ref "SPK4") (pin "P$2") (pinfunction "P$2_P$2") (pintype "bidirectional"))
    )
    (net (code "47") (name "/SPK_S5+") (class "Default")
      (node (ref "MOD5") (pin "J_SPK+") (pinfunction "SPK_J+_J_SPK+") (pintype "bidirectional"))
      (node (ref "MOD5") (pin "M_SPK1") (pinfunction "SPK_M+_M_SPK1") (pintype "bidirectional"))
      (node (ref "SKP5-8") (pin "P$1") (pinfunction "1_P$1") (pintype "bidirectional"))
      (node (ref "SPK5") (pin "P$1") (pinfunction "P$1_P$1") (pintype "bidirectional"))
    )
    (net (code "48") (name "/SPK_S5-") (class "Default")
      (node (ref "MOD5") (pin "J_SPK-") (pinfunction "SPK_J-_J_SPK-") (pintype "bidirectional"))
      (node (ref "MOD5") (pin "M_SPK2") (pinfunction "SPK_M-_M_SPK2") (pintype "bidirectional"))
      (node (ref "SKP5-8") (pin "P$2") (pinfunction "2_P$2") (pintype "bidirectional"))
      (node (ref "SPK5") (pin "P$2") (pinfunction "P$2_P$2") (pintype "bidirectional"))
    )
    (net (code "49") (name "/SPK_S6+") (class "Default")
      (node (ref "MOD6") (pin "J_SPK+") (pinfunction "SPK_J+_J_SPK+") (pintype "bidirectional"))
      (node (ref "MOD6") (pin "M_SPK1") (pinfunction "SPK_M+_M_SPK1") (pintype "bidirectional"))
      (node (ref "SKP5-8") (pin "P$3") (pinfunction "1_P$3") (pintype "bidirectional"))
      (node (ref "SPK6") (pin "P$1") (pinfunction "P$1_P$1") (pintype "bidirectional"))
    )
    (net (code "50") (name "/SPK_S6-") (class "Default")
      (node (ref "MOD6") (pin "J_SPK-") (pinfunction "SPK_J-_J_SPK-") (pintype "bidirectional"))
      (node (ref "MOD6") (pin "M_SPK2") (pinfunction "SPK_M-_M_SPK2") (pintype "bidirectional"))
      (node (ref "SKP5-8") (pin "P$4") (pinfunction "2_P$4") (pintype "bidirectional"))
      (node (ref "SPK6") (pin "P$2") (pinfunction "P$2_P$2") (pintype "bidirectional"))
    )
    (net (code "51") (name "/SPK_S7+") (class "Default")
      (node (ref "MOD7") (pin "J_SPK+") (pinfunction "SPK_J+_J_SPK+") (pintype "bidirectional"))
      (node (ref "MOD7") (pin "M_SPK1") (pinfunction "SPK_M+_M_SPK1") (pintype "bidirectional"))
      (node (ref "SKP5-8") (pin "P$5") (pinfunction "1_P$5") (pintype "bidirectional"))
      (node (ref "SPK7") (pin "P$1") (pinfunction "P$1_P$1") (pintype "bidirectional"))
    )
    (net (code "52") (name "/SPK_S7-") (class "Default")
      (node (ref "MOD7") (pin "J_SPK-") (pinfunction "SPK_J-_J_SPK-") (pintype "bidirectional"))
      (node (ref "MOD7") (pin "M_SPK2") (pinfunction "SPK_M-_M_SPK2") (pintype "bidirectional"))
      (node (ref "SKP5-8") (pin "P$6") (pinfunction "2_P$6") (pintype "bidirectional"))
      (node (ref "SPK7") (pin "P$2") (pinfunction "P$2_P$2") (pintype "bidirectional"))
    )
    (net (code "53") (name "/SPK_S8+") (class "Default")
      (node (ref "MOD8") (pin "J_SPK+") (pinfunction "SPK_J+_J_SPK+") (pintype "bidirectional"))
      (node (ref "MOD8") (pin "M_SPK1") (pinfunction "SPK_M+_M_SPK1") (pintype "bidirectional"))
      (node (ref "SKP5-8") (pin "P$7") (pinfunction "1_P$7") (pintype "bidirectional"))
      (node (ref "SPK8") (pin "P$1") (pinfunction "P$1_P$1") (pintype "bidirectional"))
    )
    (net (code "54") (name "/SPK_S8-") (class "Default")
      (node (ref "MOD8") (pin "J_SPK-") (pinfunction "SPK_J-_J_SPK-") (pintype "bidirectional"))
      (node (ref "MOD8") (pin "M_SPK2") (pinfunction "SPK_M-_M_SPK2") (pintype "bidirectional"))
      (node (ref "SKP5-8") (pin "P$8") (pinfunction "2_P$8") (pintype "bidirectional"))
      (node (ref "SPK8") (pin "P$2") (pinfunction "P$2_P$2") (pintype "bidirectional"))
    )
    (net (code "56") (name "GND") (class "Default")
      (node (ref "C1") (pin "2") (pinfunction "2_2") (pintype "passive"))
      (node (ref "C11") (pin "-") (pinfunction "-_-") (pintype "passive"))
      (node (ref "C12") (pin "-") (pinfunction "-_-") (pintype "passive"))
      (node (ref "C13") (pin "-") (pinfunction "-_-") (pintype "passive"))
      (node (ref "C14") (pin "-") (pinfunction "-_-") (pintype "passive"))
      (node (ref "C15") (pin "-") (pinfunction "-_-") (pintype "passive"))
      (node (ref "C16") (pin "-") (pinfunction "-_-") (pintype "passive"))
      (node (ref "C17") (pin "-") (pinfunction "-_-") (pintype "passive"))
      (node (ref "C18") (pin "-") (pinfunction "-_-") (pintype "passive"))
      (node (ref "C2") (pin "2") (pinfunction "2_2") (pintype "passive"))
      (node (ref "C3") (pin "2") (pinfunction "2_2") (pintype "passive"))
      (node (ref "C4") (pin "2") (pinfunction "2_2") (pintype "passive"))
      (node (ref "C5") (pin "2") (pinfunction "2_2") (pintype "passive"))
      (node (ref "C6") (pin "2") (pinfunction "2_2") (pintype "passive"))
      (node (ref "C7") (pin "2") (pinfunction "2_2") (pintype "passive"))
      (node (ref "C8") (pin "2") (pinfunction "2_2") (pintype "passive"))
      (node (ref "D1") (pin "K") (pinfunction "C_K") (pintype "passive"))
      (node (ref "DAC1") (pin "P$2") (pinfunction "P$2_P$2") (pintype "bidirectional"))
      (node (ref "DAC2") (pin "P$2") (pinfunction "P$2_P$2") (pintype "bidirectional"))
      (node (ref "DAC3") (pin "P$2") (pinfunction "P$2_P$2") (pintype "bidirectional"))
      (node (ref "DAC4") (pin "P$2") (pinfunction "P$2_P$2") (pintype "bidirectional"))
      (node (ref "DAC5") (pin "P$2") (pinfunction "P$2_P$2") (pintype "bidirectional"))
      (node (ref "DAC6") (pin "P$2") (pinfunction "P$2_P$2") (pintype "bidirectional"))
      (node (ref "DAC7") (pin "P$2") (pinfunction "P$2_P$2") (pintype "bidirectional"))
      (node (ref "DAC8") (pin "P$2") (pinfunction "P$2_P$2") (pintype "bidirectional"))
      (node (ref "KEY80") (pin "14") (pinfunction "GND_14") (pintype "power_in"))
      (node (ref "MOD1") (pin "J_GND1") (pinfunction "GNDJ1_J_GND1") (pintype "power_in"))
      (node (ref "MOD1") (pin "M_GND1") (pinfunction "GNDM1_M_GND1") (pintype "power_in"))
      (node (ref "MOD2") (pin "J_GND1") (pinfunction "GNDJ1_J_GND1") (pintype "power_in"))
      (node (ref "MOD2") (pin "M_GND1") (pinfunction "GNDM1_M_GND1") (pintype "power_in"))
      (node (ref "MOD3") (pin "J_GND1") (pinfunction "GNDJ1_J_GND1") (pintype "power_in"))
      (node (ref "MOD3") (pin "M_GND1") (pinfunction "GNDM1_M_GND1") (pintype "power_in"))
      (node (ref "MOD4") (pin "J_GND1") (pinfunction "GNDJ1_J_GND1") (pintype "power_in"))
      (node (ref "MOD4") (pin "M_GND1") (pinfunction "GNDM1_M_GND1") (pintype "power_in"))
      (node (ref "MOD5") (pin "J_GND1") (pinfunction "GNDJ1_J_GND1") (pintype "power_in"))
      (node (ref "MOD5") (pin "M_GND1") (pinfunction "GNDM1_M_GND1") (pintype "power_in"))
      (node (ref "MOD6") (pin "J_GND1") (pinfunction "GNDJ1_J_GND1") (pintype "power_in"))
      (node (ref "MOD6") (pin "M_GND1") (pinfunction "GNDM1_M_GND1") (pintype "power_in"))
      (node (ref "MOD7") (pin "J_GND1") (pinfunction "GNDJ1_J_GND1") (pintype "power_in"))
      (node (ref "MOD7") (pin "M_GND1") (pinfunction "GNDM1_M_GND1") (pintype "power_in"))
      (node (ref "MOD8") (pin "J_GND1") (pinfunction "GNDJ1_J_GND1") (pintype "power_in"))
      (node (ref "MOD8") (pin "M_GND1") (pinfunction "GNDM1_M_GND1") (pintype "power_in"))
      (node (ref "SJ1") (pin "1") (pinfunction "1_1") (pintype "passive"))
      (node (ref "SJ2") (pin "1") (pinfunction "1_1") (pintype "passive"))
      (node (ref "SJ3") (pin "1") (pinfunction "1_1") (pintype "passive"))
      (node (ref "SJ4") (pin "1") (pinfunction "1_1") (pintype "passive"))
      (node (ref "SJ5") (pin "1") (pinfunction "1_1") (pintype "passive"))
      (node (ref "SJ6") (pin "1") (pinfunction "1_1") (pintype "passive"))
      (node (ref "SJ7") (pin "1") (pinfunction "1_1") (pintype "passive"))
      (node (ref "SJ8") (pin "1") (pinfunction "1_1") (pintype "passive"))
      (node (ref "X1") (pin "1") (pinfunction "KL_1") (pintype "passive"))
      (node (ref "X1") (pin "M") (pinfunction "KL_M") (pintype "passive"))
    )
    (net (code "57") (name "Net-(D1-PadA)") (class "Default")
      (node (ref "D1") (pin "A") (pinfunction "A_A") (pintype "passive"))
      (node (ref "R9") (pin "2") (pinfunction "2_2") (pintype "passive"))
    )
    (net (code "58") (name "Net-(KEY80-VCC)") (class "Default")
      (node (ref "JP_POWER") (pin "1") (pinfunction "1_1") (pintype "passive"))
      (node (ref "KEY80") (pin "13") (pinfunction "VCC_13") (pintype "power_in"))
    )
    (net (code "59") (name "Net-(MOD1-GNDM2)") (class "Default")
      (node (ref "MOD1") (pin "M_GND2") (pinfunction "GNDM2_M_GND2") (pintype "power_in"))
      (node (ref "SJ1") (pin "2") (pinfunction "2_2") (pintype "passive"))
    )
    (net (code "60") (name "Net-(MOD1-VCCJ)") (class "Default")
      (node (ref "C1") (pin "1") (pinfunction "1_1") (pintype "passive"))
      (node (ref "C11") (pin "+") (pinfunction "+_+") (pintype "passive"))
      (node (ref "MOD1") (pin "J_VCC") (pinfunction "VCCJ_J_VCC") (pintype "power_in"))
      (node (ref "MOD1") (pin "M_VCC") (pinfunction "VCCM_M_VCC") (pintype "power_in"))
      (node (ref "R11") (pin "1") (pinfunction "1_1") (pintype "passive"))
    )
    (net (code "61") (name "Net-(MOD2-GNDM2)") (class "Default")
      (node (ref "MOD2") (pin "M_GND2") (pinfunction "GNDM2_M_GND2") (pintype "power_in"))
      (node (ref "SJ2") (pin "2") (pinfunction "2_2") (pintype "passive"))
    )
    (net (code "62") (name "Net-(MOD2-RXJ)") (class "Default")
      (node (ref "MOD2") (pin "J_RX") (pinfunction "RXJ_J_RX") (pintype "bidirectional"))
      (node (ref "MOD2") (pin "M_RX") (pinfunction "RXM_M_RX") (pintype "bidirectional"))
      (node (ref "R2") (pin "2") (pinfunction "2_2") (pintype "passive"))
    )
    (net (code "63") (name "Net-(MOD2-VCCJ)") (class "Default")
      (node (ref "C12") (pin "+") (pinfunction "+_+") (pintype "passive"))
      (node (ref "C2") (pin "1") (pinfunction "1_1") (pintype "passive"))
      (node (ref "MOD2") (pin "J_VCC") (pinfunction "VCCJ_J_VCC") (pintype "power_in"))
      (node (ref "MOD2") (pin "M_VCC") (pinfunction "VCCM_M_VCC") (pintype "power_in"))
      (node (ref "R12") (pin "2") (pinfunction "2_2") (pintype "passive"))
    )
    (net (code "64") (name "Net-(MOD3-GNDM2)") (class "Default")
      (node (ref "MOD3") (pin "M_GND2") (pinfunction "GNDM2_M_GND2") (pintype "power_in"))
      (node (ref "SJ3") (pin "2") (pinfunction "2_2") (pintype "passive"))
    )
    (net (code "65") (name "Net-(MOD3-RXJ)") (class "Default")
      (node (ref "MOD3") (pin "J_RX") (pinfunction "RXJ_J_RX") (pintype "bidirectional"))
      (node (ref "MOD3") (pin "M_RX") (pinfunction "RXM_M_RX") (pintype "bidirectional"))
      (node (ref "R3") (pin "2") (pinfunction "2_2") (pintype "passive"))
    )
    (net (code "66") (name "Net-(MOD3-VCCJ)") (class "Default")
      (node (ref "C13") (pin "+") (pinfunction "+_+") (pintype "passive"))
      (node (ref "C3") (pin "1") (pinfunction "1_1") (pintype "passive"))
      (node (ref "MOD3") (pin "J_VCC") (pinfunction "VCCJ_J_VCC") (pintype "power_in"))
      (node (ref "MOD3") (pin "M_VCC") (pinfunction "VCCM_M_VCC") (pintype "power_in"))
      (node (ref "R13") (pin "2") (pinfunction "2_2") (pintype "passive"))
    )
    (net (code "67") (name "Net-(MOD4-GNDM2)") (class "Default")
      (node (ref "MOD4") (pin "M_GND2") (pinfunction "GNDM2_M_GND2") (pintype "power_in"))
      (node (ref "SJ4") (pin "2") (pinfunction "2_2") (pintype "passive"))
    )
    (net (code "68") (name "Net-(MOD4-RXJ)") (class "Default")
      (node (ref "MOD4") (pin "J_RX") (pinfunction "RXJ_J_RX") (pintype "bidirectional"))
      (node (ref "MOD4") (pin "M_RX") (pinfunction "RXM_M_RX") (pintype "bidirectional"))
      (node (ref "R4") (pin "2") (pinfunction "2_2") (pintype "passive"))
    )
    (net (code "69") (name "Net-(MOD4-VCCJ)") (class "Default")
      (node (ref "C14") (pin "+") (pinfunction "+_+") (pintype "passive"))
      (node (ref "C4") (pin "1") (pinfunction "1_1") (pintype "passive"))
      (node (ref "MOD4") (pin "J_VCC") (pinfunction "VCCJ_J_VCC") (pintype "power_in"))
      (node (ref "MOD4") (pin "M_VCC") (pinfunction "VCCM_M_VCC") (pintype "power_in"))
      (node (ref "R14") (pin "2") (pinfunction "2_2") (pintype "passive"))
    )
    (net (code "70") (name "Net-(MOD5-GNDM2)") (class "Default")
      (node (ref "MOD5") (pin "M_GND2") (pinfunction "GNDM2_M_GND2") (pintype "power_in"))
      (node (ref "SJ5") (pin "2") (pinfunction "2_2") (pintype "passive"))
    )
    (net (code "71") (name "Net-(MOD5-RXJ)") (class "Default")
      (node (ref "MOD5") (pin "J_RX") (pinfunction "RXJ_J_RX") (pintype "bidirectional"))
      (node (ref "MOD5") (pin "M_RX") (pinfunction "RXM_M_RX") (pintype "bidirectional"))
      (node (ref "R5") (pin "2") (pinfunction "2_2") (pintype "passive"))
    )
    (net (code "72") (name "Net-(MOD5-VCCJ)") (class "Default")
      (node (ref "C15") (pin "+") (pinfunction "+_+") (pintype "passive"))
      (node (ref "C5") (pin "1") (pinfunction "1_1") (pintype "passive"))
      (node (ref "MOD5") (pin "J_VCC") (pinfunction "VCCJ_J_VCC") (pintype "power_in"))
      (node (ref "MOD5") (pin "M_VCC") (pinfunction "VCCM_M_VCC") (pintype "power_in"))
      (node (ref "R15") (pin "2") (pinfunction "2_2") (pintype "passive"))
    )
    (net (code "73") (name "Net-(MOD6-GNDM2)") (class "Default")
      (node (ref "MOD6") (pin "M_GND2") (pinfunction "GNDM2_M_GND2") (pintype "power_in"))
      (node (ref "SJ6") (pin "2") (pinfunction "2_2") (pintype "passive"))
    )
    (net (code "74") (name "Net-(MOD6-RXJ)") (class "Default")
      (node (ref "MOD6") (pin "J_RX") (pinfunction "RXJ_J_RX") (pintype "bidirectional"))
      (node (ref "MOD6") (pin "M_RX") (pinfunction "RXM_M_RX") (pintype "bidirectional"))
      (node (ref "R6") (pin "2") (pinfunction "2_2") (pintype "passive"))
    )
    (net (code "75") (name "Net-(MOD6-VCCJ)") (class "Default")
      (node (ref "C16") (pin "+") (pinfunction "+_+") (pintype "passive"))
      (node (ref "C6") (pin "1") (pinfunction "1_1") (pintype "passive"))
      (node (ref "MOD6") (pin "J_VCC") (pinfunction "VCCJ_J_VCC") (pintype "power_in"))
      (node (ref "MOD6") (pin "M_VCC") (pinfunction "VCCM_M_VCC") (pintype "power_in"))
      (node (ref "R16") (pin "2") (pinfunction "2_2") (pintype "passive"))
    )
    (net (code "76") (name "Net-(MOD7-GNDM2)") (class "Default")
      (node (ref "MOD7") (pin "M_GND2") (pinfunction "GNDM2_M_GND2") (pintype "power_in"))
      (node (ref "SJ7") (pin "2") (pinfunction "2_2") (pintype "passive"))
    )
    (net (code "77") (name "Net-(MOD7-RXJ)") (class "Default")
      (node (ref "MOD7") (pin "J_RX") (pinfunction "RXJ_J_RX") (pintype "bidirectional"))
      (node (ref "MOD7") (pin "M_RX") (pinfunction "RXM_M_RX") (pintype "bidirectional"))
      (node (ref "R7") (pin "2") (pinfunction "2_2") (pintype "passive"))
    )
    (net (code "78") (name "Net-(MOD7-VCCJ)") (class "Default")
      (node (ref "C17") (pin "+") (pinfunction "+_+") (pintype "passive"))
      (node (ref "C7") (pin "1") (pinfunction "1_1") (pintype "passive"))
      (node (ref "MOD7") (pin "J_VCC") (pinfunction "VCCJ_J_VCC") (pintype "power_in"))
      (node (ref "MOD7") (pin "M_VCC") (pinfunction "VCCM_M_VCC") (pintype "power_in"))
      (node (ref "R17") (pin "2") (pinfunction "2_2") (pintype "passive"))
    )
    (net (code "79") (name "Net-(MOD8-GNDM2)") (class "Default")
      (node (ref "MOD8") (pin "M_GND2") (pinfunction "GNDM2_M_GND2") (pintype "power_in"))
      (node (ref "SJ8") (pin "2") (pinfunction "2_2") (pintype "passive"))
    )
    (net (code "80") (name "Net-(MOD8-RXJ)") (class "Default")
      (node (ref "MOD8") (pin "J_RX") (pinfunction "RXJ_J_RX") (pintype "bidirectional"))
      (node (ref "MOD8") (pin "M_RX") (pinfunction "RXM_M_RX") (pintype "bidirectional"))
      (node (ref "R8") (pin "2") (pinfunction "2_2") (pintype "passive"))
    )
    (net (code "81") (name "Net-(MOD8-VCCJ)") (class "Default")
      (node (ref "C18") (pin "+") (pinfunction "+_+") (pintype "passive"))
      (node (ref "C8") (pin "1") (pinfunction "1_1") (pintype "passive"))
      (node (ref "MOD8") (pin "J_VCC") (pinfunction "VCCJ_J_VCC") (pintype "power_in"))
      (node (ref "MOD8") (pin "M_VCC") (pinfunction "VCCM_M_VCC") (pintype "power_in"))
      (node (ref "R18") (pin "2") (pinfunction "2_2") (pintype "passive"))
    )
    (net (code "82") (name "unconnected-(MOD1-TXJ-PadJ_TX)") (class "Default")
      (node (ref "MOD1") (pin "J_TX") (pinfunction "TXJ_J_TX") (pintype "bidirectional"))
    )
    (net (code "83") (name "unconnected-(MOD1-TXM-PadM_TX)") (class "Default")
      (node (ref "MOD1") (pin "M_TX") (pinfunction "TXM_M_TX") (pintype "bidirectional"))
    )
    (net (code "84") (name "unconnected-(MOD1-USB+-PadMUSB+)") (class "Default")
      (node (ref "MOD1") (pin "MUSB+") (pinfunction "USB+_MUSB+") (pintype "bidirectional"))
    )
    (net (code "85") (name "unconnected-(MOD1-USB--PadMUSB-)") (class "Default")
      (node (ref "MOD1") (pin "MUSB-") (pinfunction "USB-_MUSB-") (pintype "bidirectional"))
    )
    (net (code "86") (name "unconnected-(MOD2-TXJ-PadJ_TX)") (class "Default")
      (node (ref "MOD2") (pin "J_TX") (pinfunction "TXJ_J_TX") (pintype "bidirectional"))
    )
    (net (code "87") (name "unconnected-(MOD2-TXM-PadM_TX)") (class "Default")
      (node (ref "MOD2") (pin "M_TX") (pinfunction "TXM_M_TX") (pintype "bidirectional"))
    )
    (net (code "88") (name "unconnected-(MOD2-USB+-PadMUSB+)") (class "Default")
      (node (ref "MOD2") (pin "MUSB+") (pinfunction "USB+_MUSB+") (pintype "bidirectional"))
    )
    (net (code "89") (name "unconnected-(MOD2-USB--PadMUSB-)") (class "Default")
      (node (ref "MOD2") (pin "MUSB-") (pinfunction "USB-_MUSB-") (pintype "bidirectional"))
    )
    (net (code "90") (name "unconnected-(MOD3-TXJ-PadJ_TX)") (class "Default")
      (node (ref "MOD3") (pin "J_TX") (pinfunction "TXJ_J_TX") (pintype "bidirectional"))
    )
    (net (code "91") (name "unconnected-(MOD3-TXM-PadM_TX)") (class "Default")
      (node (ref "MOD3") (pin "M_TX") (pinfunction "TXM_M_TX") (pintype "bidirectional"))
    )
    (net (code "92") (name "unconnected-(MOD3-USB+-PadMUSB+)") (class "Default")
      (node (ref "MOD3") (pin "MUSB+") (pinfunction "USB+_MUSB+") (pintype "bidirectional"))
    )
    (net (code "93") (name "unconnected-(MOD3-USB--PadMUSB-)") (class "Default")
      (node (ref "MOD3") (pin "MUSB-") (pinfunction "USB-_MUSB-") (pintype "bidirectional"))
    )
    (net (code "94") (name "unconnected-(MOD4-TXJ-PadJ_TX)") (class "Default")
      (node (ref "MOD4") (pin "J_TX") (pinfunction "TXJ_J_TX") (pintype "bidirectional"))
    )
    (net (code "95") (name "unconnected-(MOD4-TXM-PadM_TX)") (class "Default")
      (node (ref "MOD4") (pin "M_TX") (pinfunction "TXM_M_TX") (pintype "bidirectional"))
    )
    (net (code "96") (name "unconnected-(MOD4-USB+-PadMUSB+)") (class "Default")
      (node (ref "MOD4") (pin "MUSB+") (pinfunction "USB+_MUSB+") (pintype "bidirectional"))
    )
    (net (code "97") (name "unconnected-(MOD4-USB--PadMUSB-)") (class "Default")
      (node (ref "MOD4") (pin "MUSB-") (pinfunction "USB-_MUSB-") (pintype "bidirectional"))
    )
    (net (code "98") (name "unconnected-(MOD5-TXJ-PadJ_TX)") (class "Default")
      (node (ref "MOD5") (pin "J_TX") (pinfunction "TXJ_J_TX") (pintype "bidirectional"))
    )
    (net (code "99") (name "unconnected-(MOD5-TXM-PadM_TX)") (class "Default")
      (node (ref "MOD5") (pin "M_TX") (pinfunction "TXM_M_TX") (pintype "bidirectional"))
    )
    (net (code "100") (name "unconnected-(MOD5-USB+-PadMUSB+)") (class "Default")
      (node (ref "MOD5") (pin "MUSB+") (pinfunction "USB+_MUSB+") (pintype "bidirectional"))
    )
    (net (code "101") (name "unconnected-(MOD5-USB--PadMUSB-)") (class "Default")
      (node (ref "MOD5") (pin "MUSB-") (pinfunction "USB-_MUSB-") (pintype "bidirectional"))
    )
    (net (code "102") (name "unconnected-(MOD6-TXJ-PadJ_TX)") (class "Default")
      (node (ref "MOD6") (pin "J_TX") (pinfunction "TXJ_J_TX") (pintype "bidirectional"))
    )
    (net (code "103") (name "unconnected-(MOD6-TXM-PadM_TX)") (class "Default")
      (node (ref "MOD6") (pin "M_TX") (pinfunction "TXM_M_TX") (pintype "bidirectional"))
    )
    (net (code "104") (name "unconnected-(MOD6-USB+-PadMUSB+)") (class "Default")
      (node (ref "MOD6") (pin "MUSB+") (pinfunction "USB+_MUSB+") (pintype "bidirectional"))
    )
    (net (code "105") (name "unconnected-(MOD6-USB--PadMUSB-)") (class "Default")
      (node (ref "MOD6") (pin "MUSB-") (pinfunction "USB-_MUSB-") (pintype "bidirectional"))
    )
    (net (code "106") (name "unconnected-(MOD7-TXJ-PadJ_TX)") (class "Default")
      (node (ref "MOD7") (pin "J_TX") (pinfunction "TXJ_J_TX") (pintype "bidirectional"))
    )
    (net (code "107") (name "unconnected-(MOD7-TXM-PadM_TX)") (class "Default")
      (node (ref "MOD7") (pin "M_TX") (pinfunction "TXM_M_TX") (pintype "bidirectional"))
    )
    (net (code "108") (name "unconnected-(MOD7-USB+-PadMUSB+)") (class "Default")
      (node (ref "MOD7") (pin "MUSB+") (pinfunction "USB+_MUSB+") (pintype "bidirectional"))
    )
    (net (code "109") (name "unconnected-(MOD7-USB--PadMUSB-)") (class "Default")
      (node (ref "MOD7") (pin "MUSB-") (pinfunction "USB-_MUSB-") (pintype "bidirectional"))
    )
    (net (code "110") (name "unconnected-(MOD8-TXJ-PadJ_TX)") (class "Default")
      (node (ref "MOD8") (pin "J_TX") (pinfunction "TXJ_J_TX") (pintype "bidirectional"))
    )
    (net (code "111") (name "unconnected-(MOD8-TXM-PadM_TX)") (class "Default")
      (node (ref "MOD8") (pin "M_TX") (pinfunction "TXM_M_TX") (pintype "bidirectional"))
    )
    (net (code "112") (name "unconnected-(MOD8-USB+-PadMUSB+)") (class "Default")
      (node (ref "MOD8") (pin "MUSB+") (pinfunction "USB+_MUSB+") (pintype "bidirectional"))
    )
    (net (code "113") (name "unconnected-(MOD8-USB--PadMUSB-)") (class "Default")
      (node (ref "MOD8") (pin "MUSB-") (pinfunction "USB-_MUSB-") (pintype "bidirectional"))
    )
  )
)
